# controller.net
KiCad netlist of a schematic drawn in Altium Designer
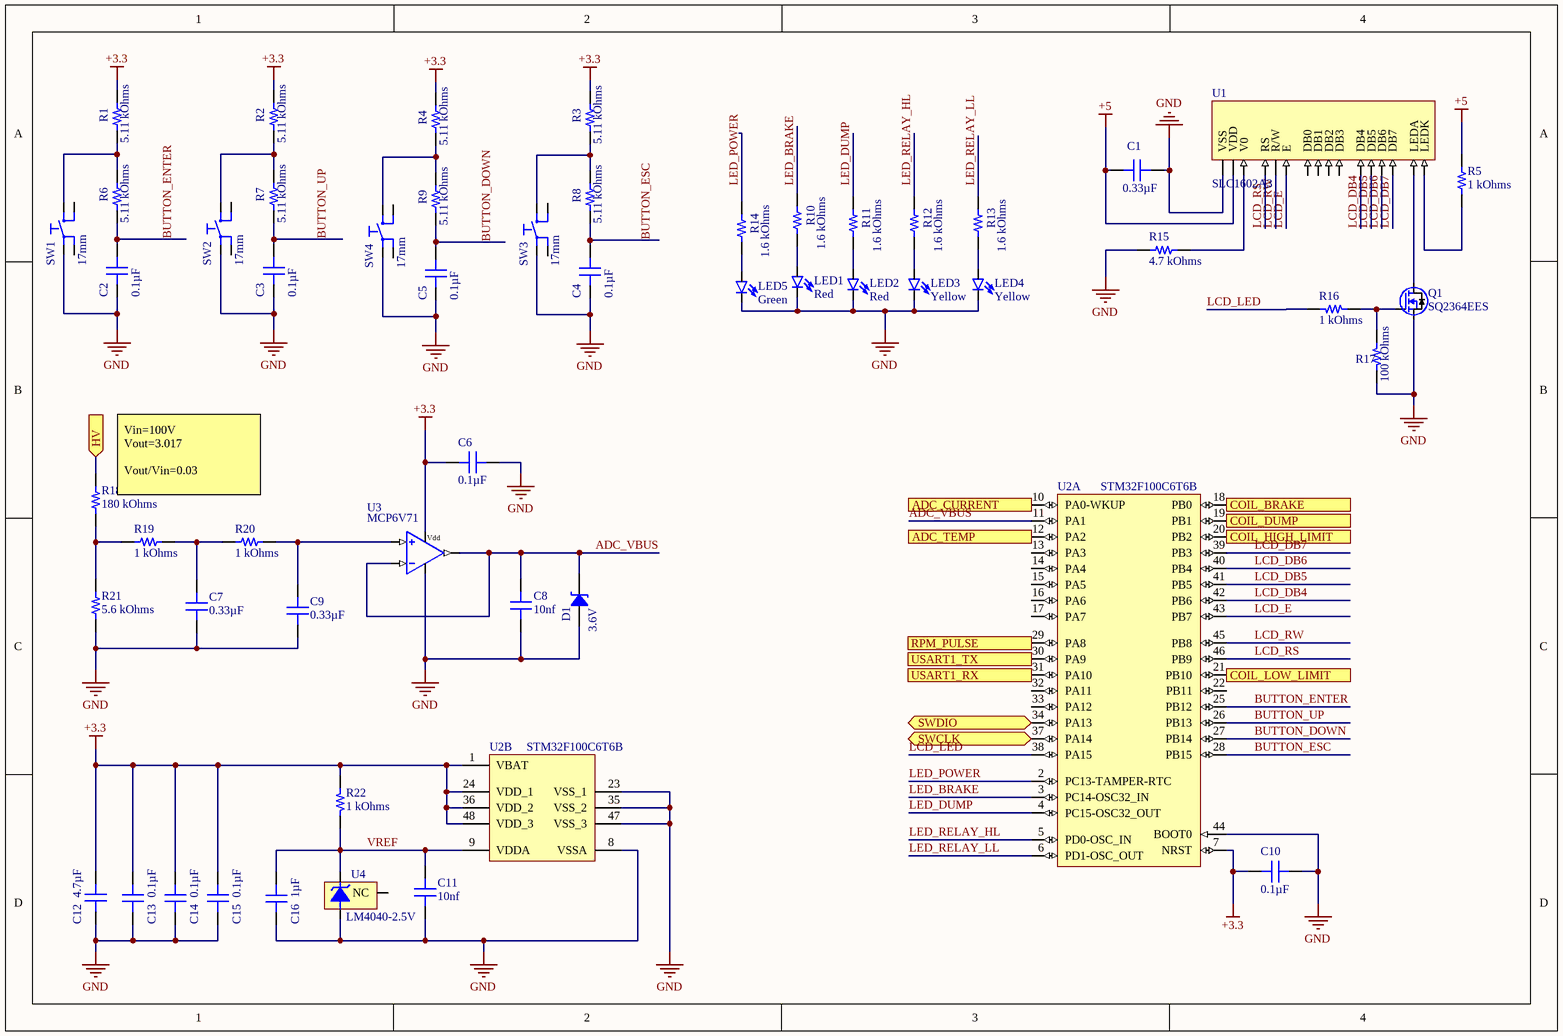
[diagram p0: controller.SchDoc]

(export (version "E")
  (design (tool "Eeschema 10.0.6"))
  (components
    (comp (ref "C1")
      (value "0.33µF")
      (footprint "CAP 0805_2012")
      (description "CAP CER 0805 330NF 50V X7R 10%")
      (fields (field (name "PART NUMBER") "C0805C334K5RECAUTO") (field (name "MANUFACTURER") "KEMET"))
      (libsource (lib "Celestial Altium Library - altium_library") (part "Capacitor"))
    )
    (comp (ref "C2")
      (value "0.1µF")
      (footprint "CAP 0603_1608")
      (description "CAP CER 0.1UF 50V X7R 0603")
      (fields
        (field (name "PART NUMBER") "CGA3E2X7R1H104K080AE")
        (field (name "MANUFACTURER") "TDK Corporation")
      )
      (libsource (lib "Celestial Altium Library - altium_library") (part "Capacitor"))
    )
    (comp (ref "C3")
      (value "0.1µF")
      (footprint "CAP 0603_1608")
      (description "CAP CER 0.1UF 50V X7R 0603")
      (fields
        (field (name "PART NUMBER") "CGA3E2X7R1H104K080AE")
        (field (name "MANUFACTURER") "TDK Corporation")
      )
      (libsource (lib "Celestial Altium Library - altium_library") (part "Capacitor"))
    )
    (comp (ref "C4")
      (value "0.1µF")
      (footprint "CAP 0603_1608")
      (description "CAP CER 0.1UF 50V X7R 0603")
      (fields
        (field (name "PART NUMBER") "CGA3E2X7R1H104K080AE")
        (field (name "MANUFACTURER") "TDK Corporation")
      )
      (libsource (lib "Celestial Altium Library - altium_library") (part "Capacitor"))
    )
    (comp (ref "C5")
      (value "0.1µF")
      (footprint "CAP 0603_1608")
      (description "CAP CER 0.1UF 50V X7R 0603")
      (fields
        (field (name "PART NUMBER") "CGA3E2X7R1H104K080AE")
        (field (name "MANUFACTURER") "TDK Corporation")
      )
      (libsource (lib "Celestial Altium Library - altium_library") (part "Capacitor"))
    )
    (comp (ref "C6")
      (value "0.1µF")
      (footprint "CAP 0603_1608")
      (description "CAP CER 0.1UF 50V X7R 0603")
      (fields
        (field (name "PART NUMBER") "CGA3E2X7R1H104K080AE")
        (field (name "MANUFACTURER") "TDK Corporation")
      )
      (libsource (lib "Celestial Altium Library - altium_library") (part "Capacitor"))
    )
    (comp (ref "C7")
      (value "0.33µF")
      (footprint "CAP 0805_2012")
      (description "CAP CER 0805 330NF 50V X7R 10%")
      (fields (field (name "PART NUMBER") "C0805C334K5RECAUTO") (field (name "MANUFACTURER") "KEMET"))
      (libsource (lib "Celestial Altium Library - altium_library") (part "Capacitor"))
    )
    (comp (ref "C8")
      (value "10nf")
      (footprint "CAP 0805_2012")
      (description "CAP CER 0805 10NF 100V X7R")
      (fields (field (name "PART NUMBER") "C0805X103K1RAC3316") (field (name "MANUFACTURER") "KEMET"))
      (libsource (lib "Celestial Altium Library - altium_library") (part "Capacitor"))
    )
    (comp (ref "C9")
      (value "0.33µF")
      (footprint "CAP 0805_2012")
      (description "CAP CER 0805 330NF 50V X7R 10%")
      (fields (field (name "PART NUMBER") "C0805C334K5RECAUTO") (field (name "MANUFACTURER") "KEMET"))
      (libsource (lib "Celestial Altium Library - altium_library") (part "Capacitor"))
    )
    (comp (ref "C10")
      (value "0.1µF")
      (footprint "CAP 0603_1608")
      (description "CAP CER 0.1UF 50V X7R 0603")
      (fields
        (field (name "PART NUMBER") "CGA3E2X7R1H104K080AE")
        (field (name "MANUFACTURER") "TDK Corporation")
      )
      (libsource (lib "Celestial Altium Library - altium_library") (part "Capacitor"))
    )
    (comp (ref "C11")
      (value "10nf")
      (footprint "CAP 0402_1005")
      (description "CAP CER 0402 10NF 16V X7R 10%")
      (fields (field (name "PART NUMBER") "C0402C103K4RECAUTO") (field (name "MANUFACTURER") "KEMET"))
      (libsource (lib "Celestial Altium Library - altium_library") (part "Capacitor"))
    )
    (comp (ref "C12")
      (value "4.7µF")
      (footprint "CAP 0805_2012")
      (description "CAP CER 4.7UF 50V X5R 0805")
      (fields
        (field (name "PART NUMBER") "CL21A475KBQNNNE")
        (field (name "MANUFACTURER") "Samsung Electro-Mechanics")
      )
      (libsource (lib "Celestial Altium Library - altium_library") (part "Capacitor"))
    )
    (comp (ref "C13")
      (value "0.1µF")
      (footprint "CAP 0603_1608")
      (description "CAP CER 0.1UF 50V X7R 0603")
      (fields
        (field (name "PART NUMBER") "CGA3E2X7R1H104K080AE")
        (field (name "MANUFACTURER") "TDK Corporation")
      )
      (libsource (lib "Celestial Altium Library - altium_library") (part "Capacitor"))
    )
    (comp (ref "C14")
      (value "0.1µF")
      (footprint "CAP 0603_1608")
      (description "CAP CER 0.1UF 50V X7R 0603")
      (fields
        (field (name "PART NUMBER") "CGA3E2X7R1H104K080AE")
        (field (name "MANUFACTURER") "TDK Corporation")
      )
      (libsource (lib "Celestial Altium Library - altium_library") (part "Capacitor"))
    )
    (comp (ref "C15")
      (value "0.1µF")
      (footprint "CAP 0603_1608")
      (description "CAP CER 0.1UF 50V X7R 0603")
      (fields
        (field (name "PART NUMBER") "CGA3E2X7R1H104K080AE")
        (field (name "MANUFACTURER") "TDK Corporation")
      )
      (libsource (lib "Celestial Altium Library - altium_library") (part "Capacitor"))
    )
    (comp (ref "C16")
      (value "1µF")
      (footprint "CAP 0805_2012")
      (description "CAP CER 1UF 50V X7R 0805")
      (fields (field (name "PART NUMBER") "08055C105K4Z2A") (field (name "MANUFACTURER") "AVX Corporation"))
      (libsource (lib "Celestial Altium Library - altium_library") (part "Capacitor"))
    )
    (comp (ref "D1")
      (value "3.6V")
      (footprint "SOD-123")
      (description "DIODE ZENER 3.6V 500MW SOD123")
      (fields (field (name "PART NUMBER") "MMSZ3V6T1G") (field (name "MANUFACTURER") "ON Semiconductor"))
      (libsource (lib "Celestial Altium Library - altium_library") (part "Diode Zener"))
    )
    (comp (ref "LED1")
      (value "Red")
      (footprint "3mm LED THT")
      (libsource (lib "My_Library_Led_Indication") (part "3mm led red THT"))
    )
    (comp (ref "LED2")
      (value "Red")
      (footprint "3mm LED THT")
      (libsource (lib "My_Library_Led_Indication") (part "3mm led red THT"))
    )
    (comp (ref "LED3")
      (value "Yellow")
      (footprint "3mm LED THT")
      (libsource (lib "My_Library_Led_Indication") (part "3mm led yellow THT"))
    )
    (comp (ref "LED4")
      (value "Yellow")
      (footprint "3mm LED THT")
      (libsource (lib "My_Library_Led_Indication") (part "3mm led yellow THT"))
    )
    (comp (ref "LED5")
      (value "Green")
      (footprint "3mm LED THT")
      (libsource (lib "My_Library_Led_Indication") (part "3mm led green THT"))
    )
    (comp (ref "Q1")
      (value "SQ2364EES")
      (footprint "SOT23-(SQ2364EES)_H")
      (description "Trans MOSFET N-CH 60V 2A Automotive 3-Pin SOT-23 T/R")
      (fields
        (field (name "MANUFACTURER") "Vishay")
        (field (name "MANUFACTURER PART NUMBER") "SQ2364EES-T1_GE3")
      )
      (libsource (lib "My_Library_Mosfet") (part "SQ2364EES"))
    )
    (comp (ref "R1")
      (value "5.11 kOhms")
      (footprint "RES 1206_3216")
      (description "RES 5.11K OHM 1% 1/4W 1206")
      (fields
        (field (name "PART NUMBER") "RK73H2BTTD5111F")
        (field (name "MANUFACTURER") "KOA Speer Electronics, Inc.")
      )
      (libsource (lib "Celestial Altium Library - altium_library") (part "Resistor"))
    )
    (comp (ref "R2")
      (value "5.11 kOhms")
      (footprint "RES 1206_3216")
      (description "RES 5.11K OHM 1% 1/4W 1206")
      (fields
        (field (name "PART NUMBER") "RK73H2BTTD5111F")
        (field (name "MANUFACTURER") "KOA Speer Electronics, Inc.")
      )
      (libsource (lib "Celestial Altium Library - altium_library") (part "Resistor"))
    )
    (comp (ref "R3")
      (value "5.11 kOhms")
      (footprint "RES 1206_3216")
      (description "RES 5.11K OHM 1% 1/4W 1206")
      (fields
        (field (name "PART NUMBER") "RK73H2BTTD5111F")
        (field (name "MANUFACTURER") "KOA Speer Electronics, Inc.")
      )
      (libsource (lib "Celestial Altium Library - altium_library") (part "Resistor"))
    )
    (comp (ref "R4")
      (value "5.11 kOhms")
      (footprint "RES 1206_3216")
      (description "RES 5.11K OHM 1% 1/4W 1206")
      (fields
        (field (name "PART NUMBER") "RK73H2BTTD5111F")
        (field (name "MANUFACTURER") "KOA Speer Electronics, Inc.")
      )
      (libsource (lib "Celestial Altium Library - altium_library") (part "Resistor"))
    )
    (comp (ref "R5")
      (value "1 kOhms")
      (footprint "RES 1206_3216")
      (description "RES SMD 1K OHM 1% 1/4W 1206")
      (fields
        (field (name "PART NUMBER") "CRG1206F1K0")
        (field (name "MANUFACTURER") "TE Connectivity Passive Product")
      )
      (libsource (lib "Celestial Altium Library - altium_library") (part "Resistor"))
    )
    (comp (ref "R6")
      (value "5.11 kOhms")
      (footprint "RES 1206_3216")
      (description "RES 5.11K OHM 1% 1/4W 1206")
      (fields
        (field (name "PART NUMBER") "RK73H2BTTD5111F")
        (field (name "MANUFACTURER") "KOA Speer Electronics, Inc.")
      )
      (libsource (lib "Celestial Altium Library - altium_library") (part "Resistor"))
    )
    (comp (ref "R7")
      (value "5.11 kOhms")
      (footprint "RES 1206_3216")
      (description "RES 5.11K OHM 1% 1/4W 1206")
      (fields
        (field (name "PART NUMBER") "RK73H2BTTD5111F")
        (field (name "MANUFACTURER") "KOA Speer Electronics, Inc.")
      )
      (libsource (lib "Celestial Altium Library - altium_library") (part "Resistor"))
    )
    (comp (ref "R8")
      (value "5.11 kOhms")
      (footprint "RES 1206_3216")
      (description "RES 5.11K OHM 1% 1/4W 1206")
      (fields
        (field (name "PART NUMBER") "RK73H2BTTD5111F")
        (field (name "MANUFACTURER") "KOA Speer Electronics, Inc.")
      )
      (libsource (lib "Celestial Altium Library - altium_library") (part "Resistor"))
    )
    (comp (ref "R9")
      (value "5.11 kOhms")
      (footprint "RES 1206_3216")
      (description "RES 5.11K OHM 1% 1/4W 1206")
      (fields
        (field (name "PART NUMBER") "RK73H2BTTD5111F")
        (field (name "MANUFACTURER") "KOA Speer Electronics, Inc.")
      )
      (libsource (lib "Celestial Altium Library - altium_library") (part "Resistor"))
    )
    (comp (ref "R10")
      (value "1.6 kOhms")
      (footprint "RES 1206_3216")
      (description "RES SMD 1.6K OHM 1% 1/4W 1206")
      (fields (field (name "PART NUMBER") "CRCW12061K60FKEA") (field (name "MANUFACTURER") "Vishay Dale"))
      (libsource (lib "Celestial Altium Library - altium_library") (part "Resistor"))
    )
    (comp (ref "R11")
      (value "1.6 kOhms")
      (footprint "RES 1206_3216")
      (description "RES SMD 1.6K OHM 1% 1/4W 1206")
      (fields (field (name "PART NUMBER") "CRCW12061K60FKEA") (field (name "MANUFACTURER") "Vishay Dale"))
      (libsource (lib "Celestial Altium Library - altium_library") (part "Resistor"))
    )
    (comp (ref "R12")
      (value "1.6 kOhms")
      (footprint "RES 1206_3216")
      (description "RES SMD 1.6K OHM 1% 1/4W 1206")
      (fields (field (name "PART NUMBER") "CRCW12061K60FKEA") (field (name "MANUFACTURER") "Vishay Dale"))
      (libsource (lib "Celestial Altium Library - altium_library") (part "Resistor"))
    )
    (comp (ref "R13")
      (value "1.6 kOhms")
      (footprint "RES 1206_3216")
      (description "RES SMD 1.6K OHM 1% 1/4W 1206")
      (fields (field (name "PART NUMBER") "CRCW12061K60FKEA") (field (name "MANUFACTURER") "Vishay Dale"))
      (libsource (lib "Celestial Altium Library - altium_library") (part "Resistor"))
    )
    (comp (ref "R14")
      (value "1.6 kOhms")
      (footprint "RES 1206_3216")
      (description "RES SMD 1.6K OHM 1% 1/4W 1206")
      (fields (field (name "PART NUMBER") "CRCW12061K60FKEA") (field (name "MANUFACTURER") "Vishay Dale"))
      (libsource (lib "Celestial Altium Library - altium_library") (part "Resistor"))
    )
    (comp (ref "R15")
      (value "4.7 kOhms")
      (footprint "RES 1206_3216")
      (description "RES SMD 4.7K OHM 1% 1/4W 1206")
      (fields
        (field (name "PART NUMBER") "CRG1206F4K7")
        (field (name "MANUFACTURER") "TE Connectivity Passive Product")
      )
      (libsource (lib "Celestial Altium Library - altium_library") (part "Resistor"))
    )
    (comp (ref "R16")
      (value "1 kOhms")
      (footprint "RES 1206_3216")
      (description "RES SMD 1K OHM 1% 1/4W 1206")
      (fields (field (name "PART NUMBER") "RC1206FR-071KL") (field (name "MANUFACTURER") "Yageo"))
      (libsource (lib "Celestial Altium Library - altium_library") (part "Resistor"))
    )
    (comp (ref "R17")
      (value "100 kOhms")
      (footprint "RES 1206_3216")
      (description "RES SMD 100K OHM 1% 1/4W 1206")
      (fields
        (field (name "PART NUMBER") "CRG1206F100K")
        (field (name "MANUFACTURER") "TE Connectivity Passive Product")
      )
      (libsource (lib "Celestial Altium Library - altium_library") (part "Resistor"))
    )
    (comp (ref "R18")
      (value "180 kOhms")
      (footprint "RES 1206_3216")
      (description "RES SMD 180K OHM 1% 1/4W 1206")
      (fields (field (name "PART NUMBER") "CRCW1206180KFKEA") (field (name "MANUFACTURER") "Vishay Dale"))
      (libsource (lib "Celestial Altium Library - altium_library") (part "Resistor"))
    )
    (comp (ref "R19")
      (value "1 kOhms")
      (footprint "RES 1206_3216")
      (description "RES SMD 1K OHM 1% 1/4W 1206")
      (fields (field (name "PART NUMBER") "RC1206FR-071KL") (field (name "MANUFACTURER") "Yageo"))
      (libsource (lib "Celestial Altium Library - altium_library") (part "Resistor"))
    )
    (comp (ref "R20")
      (value "1 kOhms")
      (footprint "RES 1206_3216")
      (description "RES SMD 1K OHM 1% 1/4W 1206")
      (fields (field (name "PART NUMBER") "RC1206FR-071KL") (field (name "MANUFACTURER") "Yageo"))
      (libsource (lib "Celestial Altium Library - altium_library") (part "Resistor"))
    )
    (comp (ref "R21")
      (value "5.6 kOhms")
      (footprint "RES 1206_3216")
      (description "RES SMD 5.6K OHM 1% 1/4W 1206")
      (fields (field (name "PART NUMBER") "CRCW12065K60FKEA") (field (name "MANUFACTURER") "Vishay Dale"))
      (libsource (lib "Celestial Altium Library - altium_library") (part "Resistor"))
    )
    (comp (ref "R22")
      (value "1 kOhms")
      (footprint "RES 1206_3216")
      (description "RES SMD 1K OHM 1% 1/4W 1206")
      (fields (field (name "PART NUMBER") "RC1206FR-071KL") (field (name "MANUFACTURER") "Yageo"))
      (libsource (lib "Celestial Altium Library - altium_library") (part "Resistor"))
    )
    (comp (ref "SW1")
      (value "17mm")
      (footprint "6x6x17_THT")
      (description "Black Button Tactile Switch, SPST-NO 50 mA @ 12 Vdc")
      (libsource (lib "My_Library_Tact_Switch") (part "6x617 THT Vertical Tact"))
    )
    (comp (ref "SW2")
      (value "17mm")
      (footprint "6x6x17_THT")
      (description "Black Button Tactile Switch, SPST-NO 50 mA @ 12 Vdc")
      (libsource (lib "My_Library_Tact_Switch") (part "6x617 THT Vertical Tact"))
    )
    (comp (ref "SW3")
      (value "17mm")
      (footprint "6x6x17_THT")
      (description "Black Button Tactile Switch, SPST-NO 50 mA @ 12 Vdc")
      (libsource (lib "My_Library_Tact_Switch") (part "6x617 THT Vertical Tact"))
    )
    (comp (ref "SW4")
      (value "17mm")
      (footprint "6x6x17_THT")
      (description "Black Button Tactile Switch, SPST-NO 50 mA @ 12 Vdc")
      (libsource (lib "My_Library_Tact_Switch") (part "6x617 THT Vertical Tact"))
    )
    (comp (ref "U1")
      (value "SLC1602A3")
      (footprint "2x16 Lcd Top Left 36x80mm")
      (description "2x16 Charecter Lcd. Top left pin placement.")
      (libsource (lib "My_Library_Display") (part "SLC1602A3"))
    )
    (comp (ref "U2")
      (value "STM32F100C6T6B")
      (footprint "STM-LQFP48_H")
      (libsource (lib "My_Library_MCU") (part "STM32F100C6T6B"))
    )
    (comp (ref "U3")
      (value "MCP6V71")
      (footprint "SOT23-5-MCP6V71_H")
      (description "MICROCHIP         MCP6V71UT-E/LTY             OP-AMP, SINGLE, 2MHZ, 1V/US, SC-70-5")
      (fields
        (field (name "MANUFACTURER") "Microchip")
        (field (name "MANUFACTURER PART NUMBER") "MCP6V71UT-E/LTY")
      )
      (libsource (lib "My_library_OpAmp") (part "MCP6V71UT-E/LTY"))
    )
    (comp (ref "U4")
      (value "LM4040-2.5V")
      (footprint "MF03A_L")
      (description "Precision Micropower Shunt Voltage Reference, 3-pin SOT-23, Pb-Free")
      (fields (field (name "MANUFACTURER") "National Semiconductor"))
      (libsource (lib "My_Library_Voltage_Reference") (part "LM4040CIM3-2.5/NOPB"))
    )
  )
  (nets
    (net (code "1") (name "+3.3") (class "Default")
      (node (ref "C10") (pin "2") (pinfunction "2_2") (pintype "passive"))
      (node (ref "C12") (pin "2") (pinfunction "2_2") (pintype "passive"))
      (node (ref "C13") (pin "2") (pinfunction "2_2") (pintype "passive"))
      (node (ref "C14") (pin "2") (pinfunction "2_2") (pintype "passive"))
      (node (ref "C15") (pin "2") (pinfunction "2_2") (pintype "passive"))
      (node (ref "C6") (pin "2") (pinfunction "2_2") (pintype "passive"))
      (node (ref "R1") (pin "2") (pinfunction "2_2") (pintype "passive"))
      (node (ref "R2") (pin "2") (pinfunction "2_2") (pintype "passive"))
      (node (ref "R22") (pin "1") (pinfunction "1_1") (pintype "passive"))
      (node (ref "R3") (pin "2") (pinfunction "2_2") (pintype "passive"))
      (node (ref "R4") (pin "2") (pinfunction "2_2") (pintype "passive"))
      (node (ref "U2") (pin "1") (pinfunction "VBAT_1") (pintype "power_in"))
      (node (ref "U2") (pin "24") (pinfunction "VDD_1_24") (pintype "power_in"))
      (node (ref "U2") (pin "36") (pinfunction "VDD_2_36") (pintype "power_in"))
      (node (ref "U2") (pin "48") (pinfunction "VDD_3_48") (pintype "power_in"))
      (node (ref "U2") (pin "7") (pinfunction "NRST_7") (pintype "bidirectional"))
      (node (ref "U3") (pin "5") (pinfunction "VDD_5") (pintype "power_in"))
    )
    (net (code "2") (name "+5") (class "Default")
      (node (ref "C1") (pin "2") (pinfunction "2_2") (pintype "passive"))
      (node (ref "R5") (pin "2") (pinfunction "2_2") (pintype "passive"))
      (node (ref "U1") (pin "2") (pinfunction "VDD_2") (pintype "power_in"))
    )
    (net (code "3") (name "/ADC_CURRENT") (class "Default")
      (node (ref "U2") (pin "10") (pinfunction "PA0-WKUP_10") (pintype "bidirectional"))
    )
    (net (code "4") (name "/ADC_TEMP") (class "Default")
      (node (ref "U2") (pin "12") (pinfunction "PA2_12") (pintype "bidirectional"))
    )
    (net (code "5") (name "/ADC_VBUS") (class "Default")
      (node (ref "C8") (pin "2") (pinfunction "2_2") (pintype "passive"))
      (node (ref "D1") (pin "2") (pinfunction "2_2") (pintype "passive"))
      (node (ref "U2") (pin "11") (pinfunction "PA1_11") (pintype "bidirectional"))
      (node (ref "U3") (pin "3") (pinfunction "Vin(-)_3") (pintype "input"))
      (node (ref "U3") (pin "4") (pinfunction "Out_4") (pintype "output"))
    )
    (net (code "6") (name "/BUTTON_DOWN") (class "Default")
      (node (ref "C5") (pin "2") (pinfunction "2_2") (pintype "passive"))
      (node (ref "R9") (pin "1") (pinfunction "1_1") (pintype "passive"))
      (node (ref "U2") (pin "27") (pinfunction "PB14_27") (pintype "bidirectional"))
    )
    (net (code "7") (name "/BUTTON_ENTER") (class "Default")
      (node (ref "C2") (pin "2") (pinfunction "2_2") (pintype "passive"))
      (node (ref "R6") (pin "1") (pinfunction "1_1") (pintype "passive"))
      (node (ref "U2") (pin "25") (pinfunction "PB12_25") (pintype "bidirectional"))
    )
    (net (code "8") (name "/BUTTON_ESC") (class "Default")
      (node (ref "C4") (pin "2") (pinfunction "2_2") (pintype "passive"))
      (node (ref "R8") (pin "1") (pinfunction "1_1") (pintype "passive"))
      (node (ref "U2") (pin "28") (pinfunction "PB15_28") (pintype "bidirectional"))
    )
    (net (code "9") (name "/BUTTON_UP") (class "Default")
      (node (ref "C3") (pin "2") (pinfunction "2_2") (pintype "passive"))
      (node (ref "R7") (pin "1") (pinfunction "1_1") (pintype "passive"))
      (node (ref "U2") (pin "26") (pinfunction "PB13_26") (pintype "bidirectional"))
    )
    (net (code "10") (name "/COIL_BRAKE") (class "Default")
      (node (ref "U2") (pin "18") (pinfunction "PB0_18") (pintype "bidirectional"))
    )
    (net (code "11") (name "/COIL_DUMP") (class "Default")
      (node (ref "U2") (pin "19") (pinfunction "PB1_19") (pintype "bidirectional"))
    )
    (net (code "12") (name "/COIL_HIGH_LIMIT") (class "Default")
      (node (ref "U2") (pin "20") (pinfunction "PB2_20") (pintype "bidirectional"))
    )
    (net (code "13") (name "/COIL_LOW_LIMIT") (class "Default")
      (node (ref "U2") (pin "21") (pinfunction "PB10_21") (pintype "bidirectional"))
    )
    (net (code "14") (name "/HV") (class "Default")
      (node (ref "R18") (pin "2") (pinfunction "2_2") (pintype "passive"))
    )
    (net (code "15") (name "/LCD_DB4") (class "Default")
      (node (ref "U1") (pin "11") (pinfunction "DB4_11") (pintype "input"))
      (node (ref "U2") (pin "42") (pinfunction "PB6_42") (pintype "bidirectional"))
    )
    (net (code "16") (name "/LCD_DB5") (class "Default")
      (node (ref "U1") (pin "12") (pinfunction "DB5_12") (pintype "input"))
      (node (ref "U2") (pin "41") (pinfunction "PB5_41") (pintype "bidirectional"))
    )
    (net (code "17") (name "/LCD_DB6") (class "Default")
      (node (ref "U1") (pin "13") (pinfunction "DB6_13") (pintype "input"))
      (node (ref "U2") (pin "40") (pinfunction "PB4_40") (pintype "bidirectional"))
    )
    (net (code "18") (name "/LCD_DB7") (class "Default")
      (node (ref "U1") (pin "14") (pinfunction "DB7_14") (pintype "input"))
      (node (ref "U2") (pin "39") (pinfunction "PB3_39") (pintype "bidirectional"))
    )
    (net (code "19") (name "/LCD_E") (class "Default")
      (node (ref "U1") (pin "6") (pinfunction "E_6") (pintype "input"))
      (node (ref "U2") (pin "43") (pinfunction "PB7_43") (pintype "bidirectional"))
    )
    (net (code "20") (name "/LCD_LED") (class "Default")
      (node (ref "R16") (pin "2") (pinfunction "2_2") (pintype "passive"))
      (node (ref "U2") (pin "38") (pinfunction "PA15_38") (pintype "bidirectional"))
    )
    (net (code "21") (name "/LCD_RS") (class "Default")
      (node (ref "U1") (pin "4") (pinfunction "RS_4") (pintype "input"))
      (node (ref "U2") (pin "46") (pinfunction "PB9_46") (pintype "bidirectional"))
    )
    (net (code "22") (name "/LCD_RW") (class "Default")
      (node (ref "U1") (pin "5") (pinfunction "R/W_5") (pintype "bidirectional"))
      (node (ref "U2") (pin "45") (pinfunction "PB8_45") (pintype "bidirectional"))
    )
    (net (code "23") (name "/LED_BRAKE") (class "Default")
      (node (ref "R10") (pin "2") (pinfunction "2_2") (pintype "passive"))
      (node (ref "U2") (pin "3") (pinfunction "PC14-OSC32_IN_3") (pintype "bidirectional"))
    )
    (net (code "24") (name "/LED_DUMP") (class "Default")
      (node (ref "R11") (pin "2") (pinfunction "2_2") (pintype "passive"))
      (node (ref "U2") (pin "4") (pinfunction "PC15-OSC32_OUT_4") (pintype "bidirectional"))
    )
    (net (code "25") (name "/LED_POWER") (class "Default")
      (node (ref "R14") (pin "2") (pinfunction "2_2") (pintype "passive"))
      (node (ref "U2") (pin "2") (pinfunction "PC13-TAMPER-RTC_2") (pintype "bidirectional"))
    )
    (net (code "26") (name "/LED_RELAY_HL") (class "Default")
      (node (ref "R12") (pin "2") (pinfunction "2_2") (pintype "passive"))
      (node (ref "U2") (pin "5") (pinfunction "PD0-OSC_IN_5") (pintype "bidirectional"))
    )
    (net (code "27") (name "/LED_RELAY_LL") (class "Default")
      (node (ref "R13") (pin "2") (pinfunction "2_2") (pintype "passive"))
      (node (ref "U2") (pin "6") (pinfunction "PD1-OSC_OUT_6") (pintype "bidirectional"))
    )
    (net (code "28") (name "/RPM_PULSE") (class "Default")
      (node (ref "U2") (pin "29") (pinfunction "PA8_29") (pintype "bidirectional"))
    )
    (net (code "29") (name "/SWCLK") (class "Default")
      (node (ref "U2") (pin "37") (pinfunction "PA14_37") (pintype "bidirectional"))
    )
    (net (code "30") (name "/SWDIO") (class "Default")
      (node (ref "U2") (pin "34") (pinfunction "PA13_34") (pintype "bidirectional"))
    )
    (net (code "31") (name "/USART1_RX") (class "Default")
      (node (ref "U2") (pin "31") (pinfunction "PA10_31") (pintype "bidirectional"))
    )
    (net (code "32") (name "/USART1_TX") (class "Default")
      (node (ref "U2") (pin "30") (pinfunction "PA9_30") (pintype "bidirectional"))
    )
    (net (code "33") (name "/VREF") (class "Default")
      (node (ref "C11") (pin "2") (pinfunction "2_2") (pintype "passive"))
      (node (ref "C16") (pin "2") (pinfunction "2_2") (pintype "passive"))
      (node (ref "R22") (pin "2") (pinfunction "2_2") (pintype "passive"))
      (node (ref "U2") (pin "9") (pinfunction "VDDA_9") (pintype "power_in"))
      (node (ref "U4") (pin "1") (pinfunction "+V_1") (pintype "passive"))
    )
    (net (code "34") (name "GND") (class "Default")
      (node (ref "C1") (pin "1") (pinfunction "1_1") (pintype "passive"))
      (node (ref "C10") (pin "1") (pinfunction "1_1") (pintype "passive"))
      (node (ref "C11") (pin "1") (pinfunction "1_1") (pintype "passive"))
      (node (ref "C12") (pin "1") (pinfunction "1_1") (pintype "passive"))
      (node (ref "C13") (pin "1") (pinfunction "1_1") (pintype "passive"))
      (node (ref "C14") (pin "1") (pinfunction "1_1") (pintype "passive"))
      (node (ref "C15") (pin "1") (pinfunction "1_1") (pintype "passive"))
      (node (ref "C16") (pin "1") (pinfunction "1_1") (pintype "passive"))
      (node (ref "C2") (pin "1") (pinfunction "1_1") (pintype "passive"))
      (node (ref "C3") (pin "1") (pinfunction "1_1") (pintype "passive"))
      (node (ref "C4") (pin "1") (pinfunction "1_1") (pintype "passive"))
      (node (ref "C5") (pin "1") (pinfunction "1_1") (pintype "passive"))
      (node (ref "C6") (pin "1") (pinfunction "1_1") (pintype "passive"))
      (node (ref "C7") (pin "1") (pinfunction "1_1") (pintype "passive"))
      (node (ref "C8") (pin "1") (pinfunction "1_1") (pintype "passive"))
      (node (ref "C9") (pin "1") (pinfunction "1_1") (pintype "passive"))
      (node (ref "D1") (pin "1") (pinfunction "1_1") (pintype "passive"))
      (node (ref "LED1") (pin "A") (pinfunction "A_A") (pintype "passive"))
      (node (ref "LED2") (pin "A") (pinfunction "A_A") (pintype "passive"))
      (node (ref "LED3") (pin "A") (pinfunction "A_A") (pintype "passive"))
      (node (ref "LED4") (pin "A") (pinfunction "A_A") (pintype "passive"))
      (node (ref "LED5") (pin "A") (pinfunction "A_A") (pintype "passive"))
      (node (ref "Q1") (pin "2") (pinfunction "S_2") (pintype "passive"))
      (node (ref "R15") (pin "1") (pinfunction "1_1") (pintype "passive"))
      (node (ref "R17") (pin "1") (pinfunction "1_1") (pintype "passive"))
      (node (ref "R21") (pin "1") (pinfunction "1_1") (pintype "passive"))
      (node (ref "SW1") (pin "1") (pinfunction "1_1") (pintype "passive"))
      (node (ref "SW2") (pin "1") (pinfunction "1_1") (pintype "passive"))
      (node (ref "SW3") (pin "1") (pinfunction "1_1") (pintype "passive"))
      (node (ref "SW4") (pin "1") (pinfunction "1_1") (pintype "passive"))
      (node (ref "U1") (pin "1") (pinfunction "VSS_1") (pintype "power_in"))
      (node (ref "U2") (pin "23") (pinfunction "VSS_1_23") (pintype "power_in"))
      (node (ref "U2") (pin "35") (pinfunction "VSS_2_35") (pintype "power_in"))
      (node (ref "U2") (pin "44") (pinfunction "BOOT0_44") (pintype "input"))
      (node (ref "U2") (pin "47") (pinfunction "VSS_3_47") (pintype "power_in"))
      (node (ref "U2") (pin "8") (pinfunction "VSSA_8") (pintype "power_in"))
      (node (ref "U3") (pin "2") (pinfunction "VSS_2") (pintype "power_in"))
      (node (ref "U4") (pin "2") (pinfunction "-V_2") (pintype "passive"))
    )
    (net (code "35") (name "Net-(C7-Pad2)") (class "Default")
      (node (ref "C7") (pin "2") (pinfunction "2_2") (pintype "passive"))
      (node (ref "R19") (pin "2") (pinfunction "2_2") (pintype "passive"))
      (node (ref "R20") (pin "1") (pinfunction "1_1") (pintype "passive"))
    )
    (net (code "36") (name "Net-(LED1-PadC)") (class "Default")
      (node (ref "LED1") (pin "C") (pinfunction "C_C") (pintype "passive"))
      (node (ref "R10") (pin "1") (pinfunction "1_1") (pintype "passive"))
    )
    (net (code "37") (name "Net-(LED2-PadC)") (class "Default")
      (node (ref "LED2") (pin "C") (pinfunction "C_C") (pintype "passive"))
      (node (ref "R11") (pin "1") (pinfunction "1_1") (pintype "passive"))
    )
    (net (code "38") (name "Net-(LED3-PadC)") (class "Default")
      (node (ref "LED3") (pin "C") (pinfunction "C_C") (pintype "passive"))
      (node (ref "R12") (pin "1") (pinfunction "1_1") (pintype "passive"))
    )
    (net (code "39") (name "Net-(LED4-PadC)") (class "Default")
      (node (ref "LED4") (pin "C") (pinfunction "C_C") (pintype "passive"))
      (node (ref "R13") (pin "1") (pinfunction "1_1") (pintype "passive"))
    )
    (net (code "40") (name "Net-(LED5-PadC)") (class "Default")
      (node (ref "LED5") (pin "C") (pinfunction "C_C") (pintype "passive"))
      (node (ref "R14") (pin "1") (pinfunction "1_1") (pintype "passive"))
    )
    (net (code "41") (name "Net-(Q1-D)") (class "Default")
      (node (ref "Q1") (pin "3") (pinfunction "D_3") (pintype "passive"))
      (node (ref "U1") (pin "15") (pinfunction "LEDA_15") (pintype "input"))
    )
    (net (code "42") (name "Net-(Q1-G)") (class "Default")
      (node (ref "Q1") (pin "1") (pinfunction "G_1") (pintype "passive"))
      (node (ref "R16") (pin "1") (pinfunction "1_1") (pintype "passive"))
      (node (ref "R17") (pin "2") (pinfunction "2_2") (pintype "passive"))
    )
    (net (code "43") (name "Net-(R1-Pad1)") (class "Default")
      (node (ref "R1") (pin "1") (pinfunction "1_1") (pintype "passive"))
      (node (ref "R6") (pin "2") (pinfunction "2_2") (pintype "passive"))
      (node (ref "SW1") (pin "2") (pinfunction "2_2") (pintype "passive"))
    )
    (net (code "44") (name "Net-(R2-Pad1)") (class "Default")
      (node (ref "R2") (pin "1") (pinfunction "1_1") (pintype "passive"))
      (node (ref "R7") (pin "2") (pinfunction "2_2") (pintype "passive"))
      (node (ref "SW2") (pin "2") (pinfunction "2_2") (pintype "passive"))
    )
    (net (code "45") (name "Net-(R3-Pad1)") (class "Default")
      (node (ref "R3") (pin "1") (pinfunction "1_1") (pintype "passive"))
      (node (ref "R8") (pin "2") (pinfunction "2_2") (pintype "passive"))
      (node (ref "SW3") (pin "2") (pinfunction "2_2") (pintype "passive"))
    )
    (net (code "46") (name "Net-(R4-Pad1)") (class "Default")
      (node (ref "R4") (pin "1") (pinfunction "1_1") (pintype "passive"))
      (node (ref "R9") (pin "2") (pinfunction "2_2") (pintype "passive"))
      (node (ref "SW4") (pin "2") (pinfunction "2_2") (pintype "passive"))
    )
    (net (code "47") (name "Net-(R18-Pad1)") (class "Default")
      (node (ref "R18") (pin "1") (pinfunction "1_1") (pintype "passive"))
      (node (ref "R19") (pin "1") (pinfunction "1_1") (pintype "passive"))
      (node (ref "R21") (pin "2") (pinfunction "2_2") (pintype "passive"))
    )
    (net (code "48") (name "Net-(U1-LEDK)") (class "Default")
      (node (ref "R5") (pin "1") (pinfunction "1_1") (pintype "passive"))
      (node (ref "U1") (pin "16") (pinfunction "LEDK_16") (pintype "input"))
    )
    (net (code "49") (name "Net-(U1-V0)") (class "Default")
      (node (ref "R15") (pin "2") (pinfunction "2_2") (pintype "passive"))
      (node (ref "U1") (pin "3") (pinfunction "V0_3") (pintype "input"))
    )
    (net (code "50") (name "Net-(U3-Vin(+))") (class "Default")
      (node (ref "C9") (pin "2") (pinfunction "2_2") (pintype "passive"))
      (node (ref "R20") (pin "2") (pinfunction "2_2") (pintype "passive"))
      (node (ref "U3") (pin "1") (pinfunction "Vin(+)_1") (pintype "input"))
    )
    (net (code "51") (name "unconnected-(SW1-Pad3)") (class "Default")
      (node (ref "SW1") (pin "3") (pinfunction "3_3") (pintype "passive"))
    )
    (net (code "52") (name "unconnected-(SW1-Pad4)") (class "Default")
      (node (ref "SW1") (pin "4") (pinfunction "4_4") (pintype "passive"))
    )
    (net (code "53") (name "unconnected-(SW2-Pad3)") (class "Default")
      (node (ref "SW2") (pin "3") (pinfunction "3_3") (pintype "passive"))
    )
    (net (code "54") (name "unconnected-(SW2-Pad4)") (class "Default")
      (node (ref "SW2") (pin "4") (pinfunction "4_4") (pintype "passive"))
    )
    (net (code "55") (name "unconnected-(SW3-Pad3)") (class "Default")
      (node (ref "SW3") (pin "3") (pinfunction "3_3") (pintype "passive"))
    )
    (net (code "56") (name "unconnected-(SW3-Pad4)") (class "Default")
      (node (ref "SW3") (pin "4") (pinfunction "4_4") (pintype "passive"))
    )
    (net (code "57") (name "unconnected-(SW4-Pad3)") (class "Default")
      (node (ref "SW4") (pin "3") (pinfunction "3_3") (pintype "passive"))
    )
    (net (code "58") (name "unconnected-(SW4-Pad4)") (class "Default")
      (node (ref "SW4") (pin "4") (pinfunction "4_4") (pintype "passive"))
    )
    (net (code "59") (name "unconnected-(U1-DB0-Pad7)") (class "Default")
      (node (ref "U1") (pin "7") (pinfunction "DB0_7") (pintype "input"))
    )
    (net (code "60") (name "unconnected-(U1-DB1-Pad8)") (class "Default")
      (node (ref "U1") (pin "8") (pinfunction "DB1_8") (pintype "input"))
    )
    (net (code "61") (name "unconnected-(U1-DB2-Pad9)") (class "Default")
      (node (ref "U1") (pin "9") (pinfunction "DB2_9") (pintype "input"))
    )
    (net (code "62") (name "unconnected-(U1-DB3-Pad10)") (class "Default")
      (node (ref "U1") (pin "10") (pinfunction "DB3_10") (pintype "input"))
    )
    (net (code "63") (name "unconnected-(U2A-PA3-Pad13)") (class "Default")
      (node (ref "U2") (pin "13") (pinfunction "PA3_13") (pintype "bidirectional"))
    )
    (net (code "64") (name "unconnected-(U2A-PA4-Pad14)") (class "Default")
      (node (ref "U2") (pin "14") (pinfunction "PA4_14") (pintype "bidirectional"))
    )
    (net (code "65") (name "unconnected-(U2A-PA5-Pad15)") (class "Default")
      (node (ref "U2") (pin "15") (pinfunction "PA5_15") (pintype "bidirectional"))
    )
    (net (code "66") (name "unconnected-(U2A-PA6-Pad16)") (class "Default")
      (node (ref "U2") (pin "16") (pinfunction "PA6_16") (pintype "bidirectional"))
    )
    (net (code "67") (name "unconnected-(U2A-PA7-Pad17)") (class "Default")
      (node (ref "U2") (pin "17") (pinfunction "PA7_17") (pintype "bidirectional"))
    )
    (net (code "68") (name "unconnected-(U2A-PA11-Pad32)") (class "Default")
      (node (ref "U2") (pin "32") (pinfunction "PA11_32") (pintype "bidirectional"))
    )
    (net (code "69") (name "unconnected-(U2A-PA12-Pad33)") (class "Default")
      (node (ref "U2") (pin "33") (pinfunction "PA12_33") (pintype "bidirectional"))
    )
    (net (code "70") (name "unconnected-(U2A-PB11-Pad22)") (class "Default")
      (node (ref "U2") (pin "22") (pinfunction "PB11_22") (pintype "bidirectional"))
    )
    (net (code "71") (name "unconnected-(U4-NC-Pad3)") (class "Default")
      (node (ref "U4") (pin "3") (pinfunction "NC_3") (pintype "passive"))
    )
  )
)
